# headers-160m.net
KiCad netlist of a schematic drawn in EAGLE
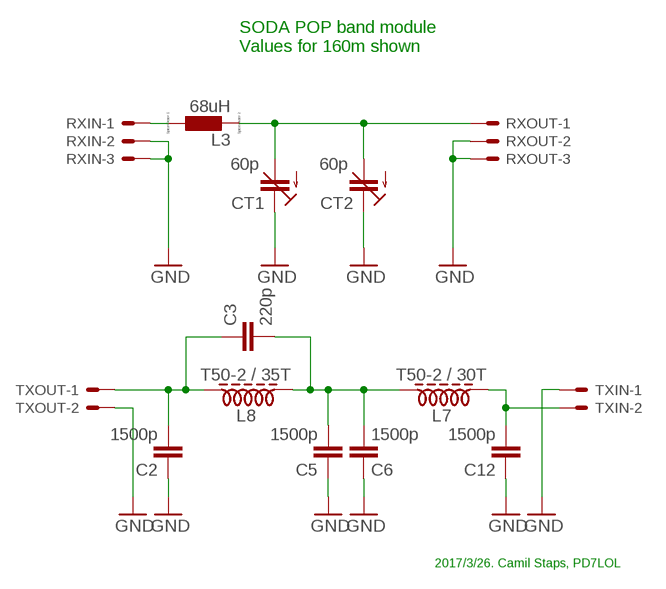
[diagram p0: schematic, sheet 1]

(export (version "E")
  (design (tool "Eeschema 10.0.6"))
  (components
    (comp (ref "C2")
      (value "1500p")
      (footprint "eagle-import:C5B2.5")
      (libsource (lib "eagle-import") (part "C5/2.5"))
    )
    (comp (ref "C3")
      (value "220p")
      (footprint "eagle-import:C5B2.5")
      (libsource (lib "eagle-import") (part "C5/2.5"))
    )
    (comp (ref "C5")
      (value "1500p")
      (footprint "eagle-import:C5B2.5")
      (libsource (lib "eagle-import") (part "C5/2.5"))
    )
    (comp (ref "C6")
      (value "1500p")
      (footprint "eagle-import:C5B2.5")
      (libsource (lib "eagle-import") (part "C5/2.5"))
    )
    (comp (ref "C12")
      (value "1500p")
      (footprint "eagle-import:C5B2.5")
      (libsource (lib "eagle-import") (part "C5/2.5"))
    )
    (comp (ref "CT1")
      (value "60p")
      (footprint "eagle-import:CTRIMTZ03")
      (libsource (lib "eagle-import") (part "C-TRIMMTZ03"))
    )
    (comp (ref "CT2")
      (value "60p")
      (footprint "eagle-import:CTRIMTZ03")
      (libsource (lib "eagle-import") (part "C-TRIMMTZ03"))
    )
    (comp (ref "L3")
      (value "68uH")
      (footprint "eagle-import:0207_10")
      (libsource (lib "eagle-import") (part "L0207/10"))
    )
    (comp (ref "L7")
      (value "T50-2 / 30T")
      (footprint "eagle-import:T30-2-28AWG-15T")
      (libsource (lib "eagle-import") (part "INDUCTORT30-2-28AWG-15T"))
    )
    (comp (ref "L8")
      (value "T50-2 / 35T")
      (footprint "eagle-import:T30-2-28AWG-15T")
      (libsource (lib "eagle-import") (part "INDUCTORT30-2-28AWG-15T"))
    )
    (comp (ref "RXIN")
      (value "22-23-2031")
      (footprint "eagle-import:22-23-2031")
      (fields (field (name "MF") "MOLEX"))
      (libsource (lib "eagle-import") (part "22-23-2031"))
    )
    (comp (ref "RXOUT")
      (value "22-23-2031")
      (footprint "eagle-import:22-23-2031")
      (fields (field (name "MF") "MOLEX"))
      (libsource (lib "eagle-import") (part "22-23-2031"))
    )
    (comp (ref "TXIN")
      (value "22-23-2021")
      (footprint "eagle-import:22-23-2021")
      (fields (field (name "MF") "MOLEX"))
      (libsource (lib "eagle-import") (part "22-23-2021"))
    )
    (comp (ref "TXOUT")
      (value "22-23-2021")
      (footprint "eagle-import:22-23-2021")
      (fields (field (name "MF") "MOLEX"))
      (libsource (lib "eagle-import") (part "22-23-2021"))
    )
  )
  (nets
    (net (code "1") (name "GND") (class "Default")
      (node (ref "C12") (pin "1") (pinfunction "1_1") (pintype "passive"))
      (node (ref "C2") (pin "1") (pinfunction "1_1") (pintype "passive"))
      (node (ref "C5") (pin "1") (pinfunction "1_1") (pintype "passive"))
      (node (ref "C6") (pin "1") (pinfunction "1_1") (pintype "passive"))
      (node (ref "CT1") (pin "1") (pinfunction "E_1") (pintype "passive"))
      (node (ref "CT2") (pin "1") (pinfunction "E_1") (pintype "passive"))
      (node (ref "RXIN") (pin "2") (pinfunction "S_2") (pintype "passive"))
      (node (ref "RXIN") (pin "3") (pinfunction "S_3") (pintype "passive"))
      (node (ref "RXOUT") (pin "2") (pinfunction "S_2") (pintype "passive"))
      (node (ref "RXOUT") (pin "3") (pinfunction "S_3") (pintype "passive"))
      (node (ref "TXIN") (pin "1") (pinfunction "S_1") (pintype "passive"))
      (node (ref "TXOUT") (pin "2") (pinfunction "S_2") (pintype "passive"))
    )
    (net (code "2") (name "Net-(CT1-A)") (class "Default")
      (node (ref "CT1") (pin "2") (pinfunction "A_2") (pintype "passive"))
      (node (ref "CT2") (pin "2") (pinfunction "A_2") (pintype "passive"))
      (node (ref "L3") (pin "2") (pinfunction "2_2") (pintype "passive"))
      (node (ref "RXOUT") (pin "1") (pinfunction "S_1") (pintype "passive"))
    )
    (net (code "3") (name "Net-(L7-1)") (class "Default")
      (node (ref "C12") (pin "2") (pinfunction "2_2") (pintype "passive"))
      (node (ref "L7") (pin "P$1") (pinfunction "1_P$1") (pintype "passive"))
      (node (ref "TXIN") (pin "2") (pinfunction "S_2") (pintype "passive"))
    )
    (net (code "4") (name "Net-(L7-2)") (class "Default")
      (node (ref "C3") (pin "2") (pinfunction "2_2") (pintype "passive"))
      (node (ref "C5") (pin "2") (pinfunction "2_2") (pintype "passive"))
      (node (ref "C6") (pin "2") (pinfunction "2_2") (pintype "passive"))
      (node (ref "L7") (pin "P$2") (pinfunction "2_P$2") (pintype "passive"))
      (node (ref "L8") (pin "P$1") (pinfunction "1_P$1") (pintype "passive"))
    )
    (net (code "5") (name "Net-(L8-2)") (class "Default")
      (node (ref "C2") (pin "2") (pinfunction "2_2") (pintype "passive"))
      (node (ref "C3") (pin "1") (pinfunction "1_1") (pintype "passive"))
      (node (ref "L8") (pin "P$2") (pinfunction "2_P$2") (pintype "passive"))
      (node (ref "TXOUT") (pin "1") (pinfunction "S_1") (pintype "passive"))
    )
    (net (code "6") (name "Net-(RXINA-S)") (class "Default")
      (node (ref "L3") (pin "1") (pinfunction "1_1") (pintype "passive"))
      (node (ref "RXIN") (pin "1") (pinfunction "S_1") (pintype "passive"))
    )
  )
)
